# Sensing.net
KiCad netlist of a schematic drawn in Altium Designer
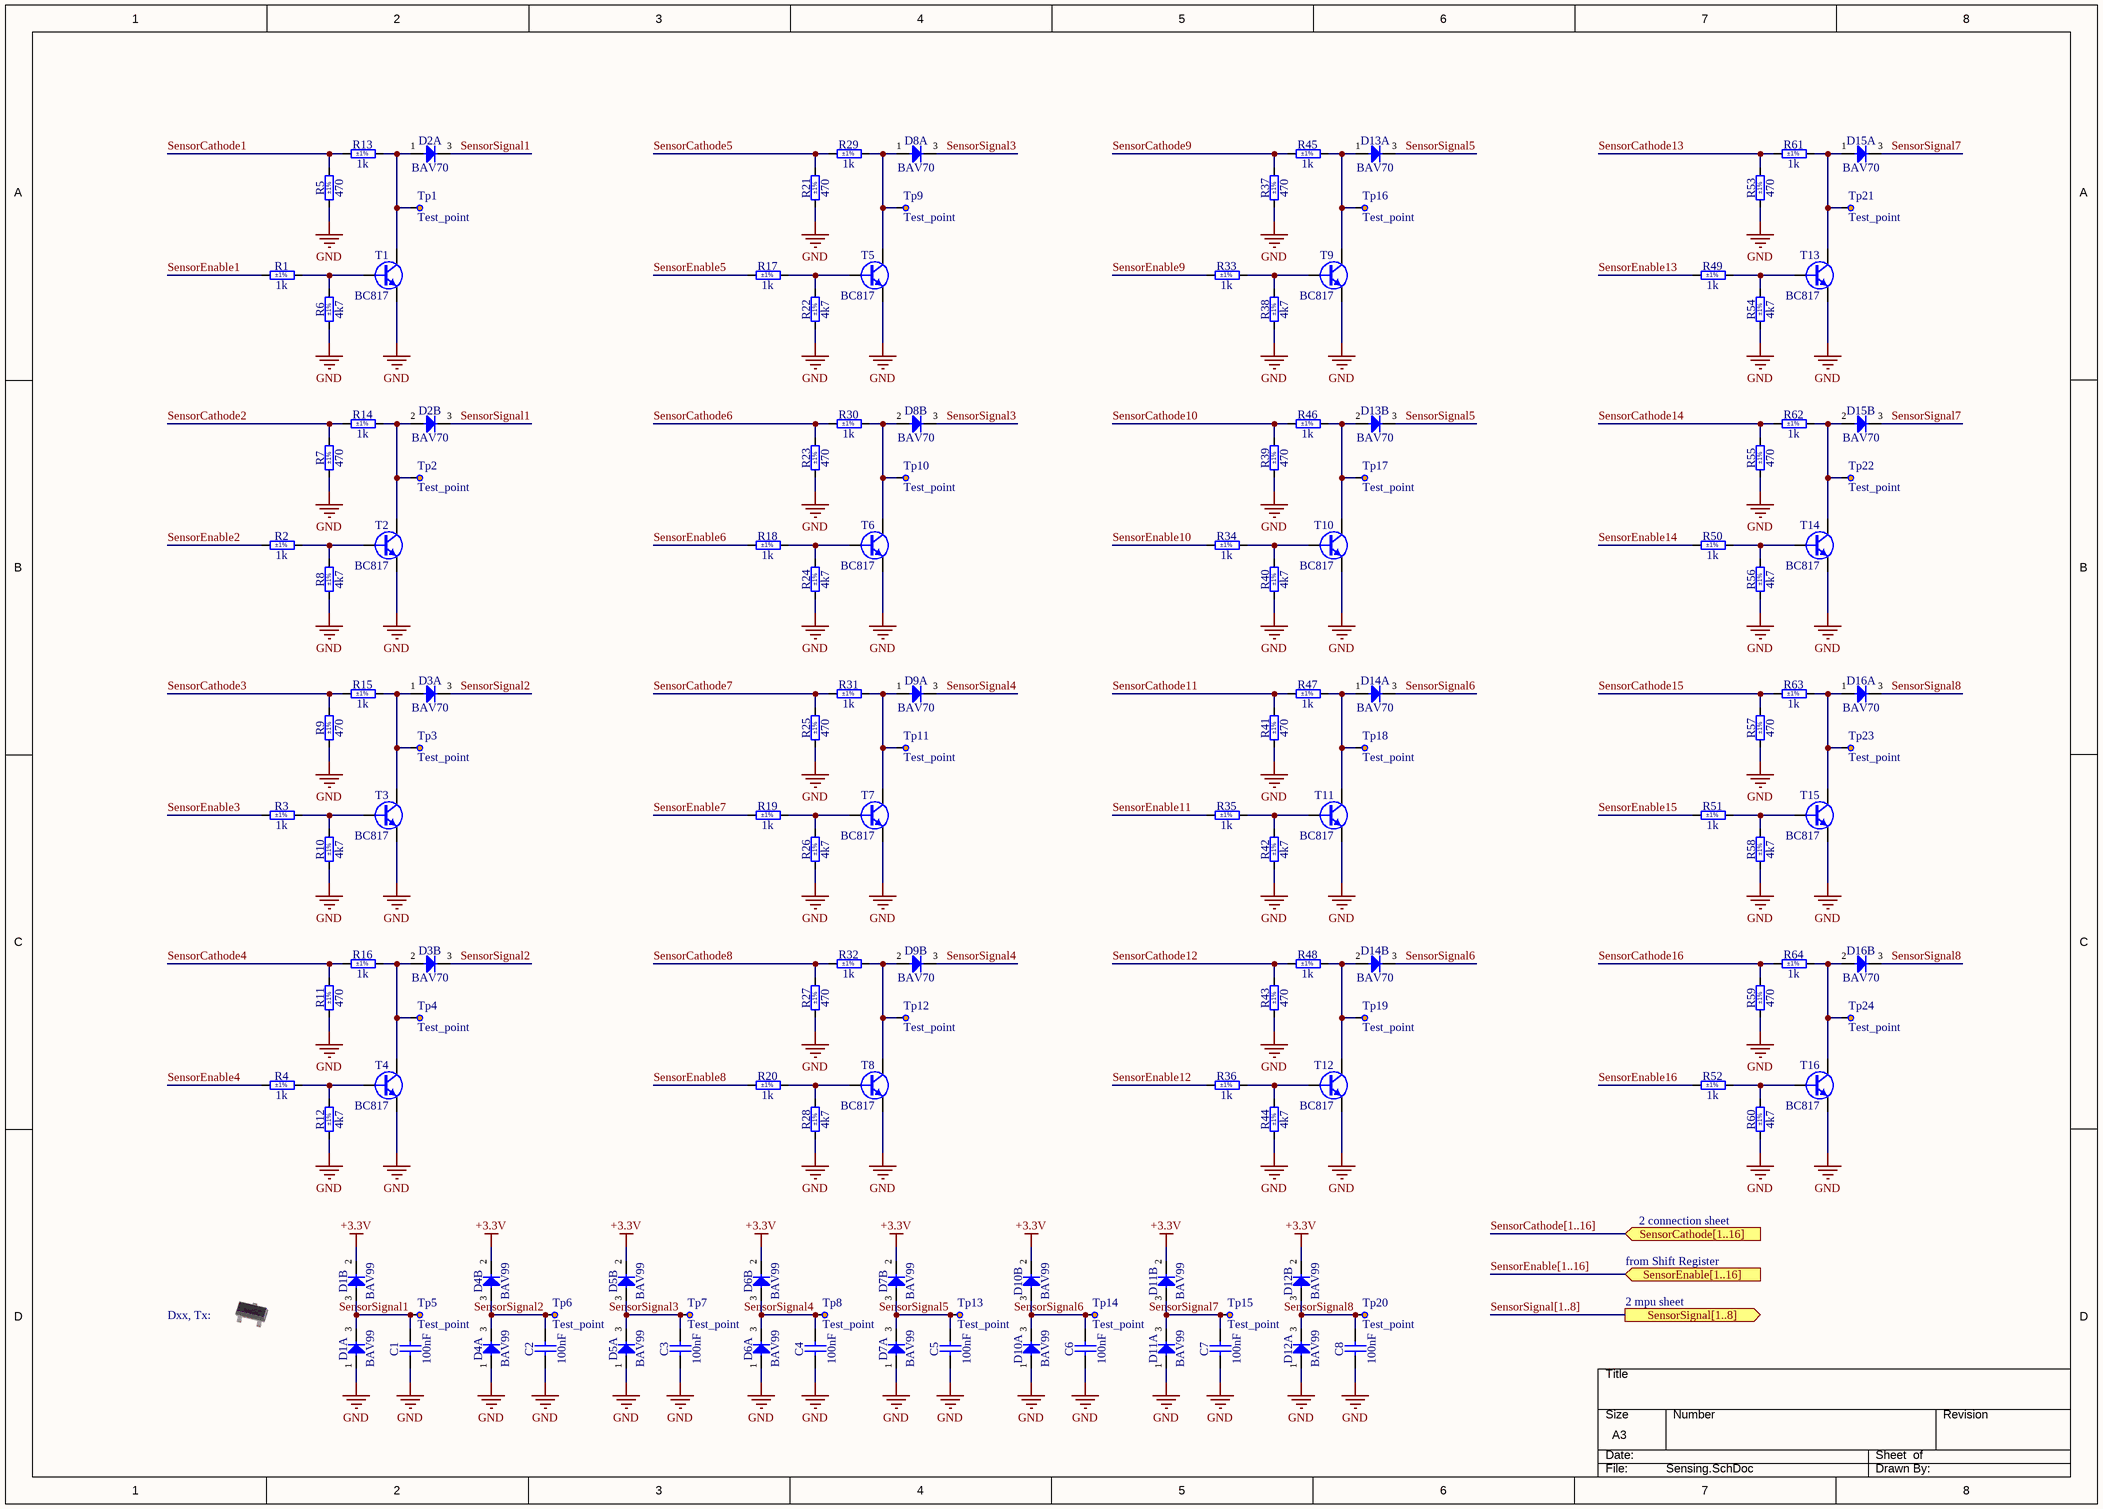
[diagram p0: Sensing.SchDoc]

(export (version "E")
  (design (tool "Eeschema 10.0.6"))
  (components
    (comp (ref "C1")
      (value "100nF")
      (footprint "CAPC1608X87N")
      (description "Non-polarised capacitor")
      (fields
        (field (name "PART NUMBER") "CC0603_100NF_50V_10%_X7R")
        (field (name "VOLTAGE") "50V")
        (field (name "AUTHOR") "CERN DEM JLC")
      )
      (libsource (lib "Capacitors") (part "Capacitor - non polarized"))
    )
    (comp (ref "C2")
      (value "100nF")
      (footprint "CAPC1608X87N")
      (description "Non-polarised capacitor")
      (fields
        (field (name "PART NUMBER") "CC0603_100NF_50V_10%_X7R")
        (field (name "VOLTAGE") "50V")
        (field (name "AUTHOR") "CERN DEM JLC")
      )
      (libsource (lib "Capacitors") (part "Capacitor - non polarized"))
    )
    (comp (ref "C3")
      (value "100nF")
      (footprint "CAPC1608X87N")
      (description "Non-polarised capacitor")
      (fields
        (field (name "PART NUMBER") "CC0603_100NF_50V_10%_X7R")
        (field (name "VOLTAGE") "50V")
        (field (name "AUTHOR") "CERN DEM JLC")
      )
      (libsource (lib "Capacitors") (part "Capacitor - non polarized"))
    )
    (comp (ref "C4")
      (value "100nF")
      (footprint "CAPC1608X87N")
      (description "Non-polarised capacitor")
      (fields
        (field (name "PART NUMBER") "CC0603_100NF_50V_10%_X7R")
        (field (name "VOLTAGE") "50V")
        (field (name "AUTHOR") "CERN DEM JLC")
      )
      (libsource (lib "Capacitors") (part "Capacitor - non polarized"))
    )
    (comp (ref "C5")
      (value "100nF")
      (footprint "CAPC1608X87N")
      (description "Non-polarised capacitor")
      (fields
        (field (name "PART NUMBER") "CC0603_100NF_50V_10%_X7R")
        (field (name "VOLTAGE") "50V")
        (field (name "AUTHOR") "CERN DEM JLC")
      )
      (libsource (lib "Capacitors") (part "Capacitor - non polarized"))
    )
    (comp (ref "C6")
      (value "100nF")
      (footprint "CAPC1608X87N")
      (description "Non-polarised capacitor")
      (fields
        (field (name "PART NUMBER") "CC0603_100NF_50V_10%_X7R")
        (field (name "VOLTAGE") "50V")
        (field (name "AUTHOR") "CERN DEM JLC")
      )
      (libsource (lib "Capacitors") (part "Capacitor - non polarized"))
    )
    (comp (ref "C7")
      (value "100nF")
      (footprint "CAPC1608X87N")
      (description "Non-polarised capacitor")
      (fields
        (field (name "PART NUMBER") "CC0603_100NF_50V_10%_X7R")
        (field (name "VOLTAGE") "50V")
        (field (name "AUTHOR") "CERN DEM JLC")
      )
      (libsource (lib "Capacitors") (part "Capacitor - non polarized"))
    )
    (comp (ref "C8")
      (value "100nF")
      (footprint "CAPC1608X87N")
      (description "Non-polarised capacitor")
      (fields
        (field (name "PART NUMBER") "CC0603_100NF_50V_10%_X7R")
        (field (name "VOLTAGE") "50V")
        (field (name "AUTHOR") "CERN DEM JLC")
      )
      (libsource (lib "Capacitors") (part "Capacitor - non polarized"))
    )
    (comp (ref "D1")
      (value "BAV99")
      (footprint "SOT95P240X110-3N")
      (description "Serial Diode")
      (fields
        (field (name "VOLTAGE") "70V")
        (field (name "POWER") "350mW")
        (field (name "AUTHOR") "CERN DEM JLC")
      )
      (libsource (lib "ICs And Semiconductors") (part "Diode x2 A1C3_A3C2"))
    )
    (comp (ref "D2")
      (value "BAV70")
      (footprint "SOT95P240X110-3N")
      (description "Dual Common Cathode Diodes")
      (fields
        (field (name "VOLTAGE") "100V")
        (field (name "MANUFACTURER") "NXP SEMICONDUCTORS")
        (field (name "AUTHOR") "CERN DEM JLC")
      )
      (libsource (lib "ICs And Semiconductors") (part "Diode x2 A1C3_A2C3"))
    )
    (comp (ref "D3")
      (value "BAV70")
      (footprint "SOT95P240X110-3N")
      (description "Dual Common Cathode Diodes")
      (fields
        (field (name "VOLTAGE") "100V")
        (field (name "MANUFACTURER") "NXP SEMICONDUCTORS")
        (field (name "AUTHOR") "CERN DEM JLC")
      )
      (libsource (lib "ICs And Semiconductors") (part "Diode x2 A1C3_A2C3"))
    )
    (comp (ref "D4")
      (value "BAV99")
      (footprint "SOT95P240X110-3N")
      (description "Serial Diode")
      (fields
        (field (name "VOLTAGE") "70V")
        (field (name "POWER") "350mW")
        (field (name "AUTHOR") "CERN DEM JLC")
      )
      (libsource (lib "ICs And Semiconductors") (part "Diode x2 A1C3_A3C2"))
    )
    (comp (ref "D5")
      (value "BAV99")
      (footprint "SOT95P240X110-3N")
      (description "Serial Diode")
      (fields
        (field (name "VOLTAGE") "70V")
        (field (name "POWER") "350mW")
        (field (name "AUTHOR") "CERN DEM JLC")
      )
      (libsource (lib "ICs And Semiconductors") (part "Diode x2 A1C3_A3C2"))
    )
    (comp (ref "D6")
      (value "BAV99")
      (footprint "SOT95P240X110-3N")
      (description "Serial Diode")
      (fields
        (field (name "VOLTAGE") "70V")
        (field (name "POWER") "350mW")
        (field (name "AUTHOR") "CERN DEM JLC")
      )
      (libsource (lib "ICs And Semiconductors") (part "Diode x2 A1C3_A3C2"))
    )
    (comp (ref "D7")
      (value "BAV99")
      (footprint "SOT95P240X110-3N")
      (description "Serial Diode")
      (fields
        (field (name "VOLTAGE") "70V")
        (field (name "POWER") "350mW")
        (field (name "AUTHOR") "CERN DEM JLC")
      )
      (libsource (lib "ICs And Semiconductors") (part "Diode x2 A1C3_A3C2"))
    )
    (comp (ref "D8")
      (value "BAV70")
      (footprint "SOT95P240X110-3N")
      (description "Dual Common Cathode Diodes")
      (fields
        (field (name "VOLTAGE") "100V")
        (field (name "MANUFACTURER") "NXP SEMICONDUCTORS")
        (field (name "AUTHOR") "CERN DEM JLC")
      )
      (libsource (lib "ICs And Semiconductors") (part "Diode x2 A1C3_A2C3"))
    )
    (comp (ref "D9")
      (value "BAV70")
      (footprint "SOT95P240X110-3N")
      (description "Dual Common Cathode Diodes")
      (fields
        (field (name "VOLTAGE") "100V")
        (field (name "MANUFACTURER") "NXP SEMICONDUCTORS")
        (field (name "AUTHOR") "CERN DEM JLC")
      )
      (libsource (lib "ICs And Semiconductors") (part "Diode x2 A1C3_A2C3"))
    )
    (comp (ref "D10")
      (value "BAV99")
      (footprint "SOT95P240X110-3N")
      (description "Serial Diode")
      (fields
        (field (name "VOLTAGE") "70V")
        (field (name "POWER") "350mW")
        (field (name "AUTHOR") "CERN DEM JLC")
      )
      (libsource (lib "ICs And Semiconductors") (part "Diode x2 A1C3_A3C2"))
    )
    (comp (ref "D11")
      (value "BAV99")
      (footprint "SOT95P240X110-3N")
      (description "Serial Diode")
      (fields
        (field (name "VOLTAGE") "70V")
        (field (name "POWER") "350mW")
        (field (name "AUTHOR") "CERN DEM JLC")
      )
      (libsource (lib "ICs And Semiconductors") (part "Diode x2 A1C3_A3C2"))
    )
    (comp (ref "D12")
      (value "BAV99")
      (footprint "SOT95P240X110-3N")
      (description "Serial Diode")
      (fields
        (field (name "VOLTAGE") "70V")
        (field (name "POWER") "350mW")
        (field (name "AUTHOR") "CERN DEM JLC")
      )
      (libsource (lib "ICs And Semiconductors") (part "Diode x2 A1C3_A3C2"))
    )
    (comp (ref "D13")
      (value "BAV70")
      (footprint "SOT95P240X110-3N")
      (description "Dual Common Cathode Diodes")
      (fields
        (field (name "VOLTAGE") "100V")
        (field (name "MANUFACTURER") "NXP SEMICONDUCTORS")
        (field (name "AUTHOR") "CERN DEM JLC")
      )
      (libsource (lib "ICs And Semiconductors") (part "Diode x2 A1C3_A2C3"))
    )
    (comp (ref "D14")
      (value "BAV70")
      (footprint "SOT95P240X110-3N")
      (description "Dual Common Cathode Diodes")
      (fields
        (field (name "VOLTAGE") "100V")
        (field (name "MANUFACTURER") "NXP SEMICONDUCTORS")
        (field (name "AUTHOR") "CERN DEM JLC")
      )
      (libsource (lib "ICs And Semiconductors") (part "Diode x2 A1C3_A2C3"))
    )
    (comp (ref "D15")
      (value "BAV70")
      (footprint "SOT95P240X110-3N")
      (description "Dual Common Cathode Diodes")
      (fields
        (field (name "VOLTAGE") "100V")
        (field (name "MANUFACTURER") "NXP SEMICONDUCTORS")
        (field (name "AUTHOR") "CERN DEM JLC")
      )
      (libsource (lib "ICs And Semiconductors") (part "Diode x2 A1C3_A2C3"))
    )
    (comp (ref "D16")
      (value "BAV70")
      (footprint "SOT95P240X110-3N")
      (description "Dual Common Cathode Diodes")
      (fields
        (field (name "VOLTAGE") "100V")
        (field (name "MANUFACTURER") "NXP SEMICONDUCTORS")
        (field (name "AUTHOR") "CERN DEM JLC")
      )
      (libsource (lib "ICs And Semiconductors") (part "Diode x2 A1C3_A2C3"))
    )
    (comp (ref "R1")
      (value "1k")
      (footprint "RESC1608X55N")
      (description "Resistor - 1%")
      (fields
        (field (name "TOLERANCE") "±1%")
        (field (name "PART NUMBER") "R0603_1K_1%_0.1W_100PPM")
        (field (name "POWER") "0.1W")
        (field (name "AUTHOR") "CERN DEM JLC")
      )
      (libsource (lib "Resistors") (part "Resistor - 1%"))
    )
    (comp (ref "R2")
      (value "1k")
      (footprint "RESC1608X55N")
      (description "Resistor - 1%")
      (fields
        (field (name "TOLERANCE") "±1%")
        (field (name "PART NUMBER") "R0603_1K_1%_0.1W_100PPM")
        (field (name "POWER") "0.1W")
        (field (name "AUTHOR") "CERN DEM JLC")
      )
      (libsource (lib "Resistors") (part "Resistor - 1%"))
    )
    (comp (ref "R3")
      (value "1k")
      (footprint "RESC1608X55N")
      (description "Resistor - 1%")
      (fields
        (field (name "TOLERANCE") "±1%")
        (field (name "PART NUMBER") "R0603_1K_1%_0.1W_100PPM")
        (field (name "POWER") "0.1W")
        (field (name "AUTHOR") "CERN DEM JLC")
      )
      (libsource (lib "Resistors") (part "Resistor - 1%"))
    )
    (comp (ref "R4")
      (value "1k")
      (footprint "RESC1608X55N")
      (description "Resistor - 1%")
      (fields
        (field (name "TOLERANCE") "±1%")
        (field (name "PART NUMBER") "R0603_1K_1%_0.1W_100PPM")
        (field (name "POWER") "0.1W")
        (field (name "AUTHOR") "CERN DEM JLC")
      )
      (libsource (lib "Resistors") (part "Resistor - 1%"))
    )
    (comp (ref "R5")
      (value "470")
      (footprint "RESC6331X70N")
      (description "Resistor - 1%")
      (fields
        (field (name "TOLERANCE") "±1%")
        (field (name "PART NUMBER") "R2512_470R_1%_1W_100PPM")
        (field (name "POWER") "1W")
        (field (name "AUTHOR") "CERN DEM BC")
      )
      (libsource (lib "Resistors") (part "Resistor - 1%"))
    )
    (comp (ref "R6")
      (value "4k7")
      (footprint "RESC1608X55N")
      (description "Resistor - 1%")
      (fields
        (field (name "TOLERANCE") "±1%")
        (field (name "PART NUMBER") "R0603_4K7_1%_0.1W_100PPM")
        (field (name "POWER") "0.1W")
        (field (name "AUTHOR") "CERN DEM JLC")
      )
      (libsource (lib "Resistors") (part "Resistor - 1%"))
    )
    (comp (ref "R7")
      (value "470")
      (footprint "RESC6331X70N")
      (description "Resistor - 1%")
      (fields
        (field (name "TOLERANCE") "±1%")
        (field (name "PART NUMBER") "R2512_470R_1%_1W_100PPM")
        (field (name "POWER") "1W")
        (field (name "AUTHOR") "CERN DEM BC")
      )
      (libsource (lib "Resistors") (part "Resistor - 1%"))
    )
    (comp (ref "R8")
      (value "4k7")
      (footprint "RESC1608X55N")
      (description "Resistor - 1%")
      (fields
        (field (name "TOLERANCE") "±1%")
        (field (name "PART NUMBER") "R0603_4K7_1%_0.1W_100PPM")
        (field (name "POWER") "0.1W")
        (field (name "AUTHOR") "CERN DEM JLC")
      )
      (libsource (lib "Resistors") (part "Resistor - 1%"))
    )
    (comp (ref "R9")
      (value "470")
      (footprint "RESC6331X70N")
      (description "Resistor - 1%")
      (fields
        (field (name "TOLERANCE") "±1%")
        (field (name "PART NUMBER") "R2512_470R_1%_1W_100PPM")
        (field (name "POWER") "1W")
        (field (name "AUTHOR") "CERN DEM BC")
      )
      (libsource (lib "Resistors") (part "Resistor - 1%"))
    )
    (comp (ref "R10")
      (value "4k7")
      (footprint "RESC1608X55N")
      (description "Resistor - 1%")
      (fields
        (field (name "TOLERANCE") "±1%")
        (field (name "PART NUMBER") "R0603_4K7_1%_0.1W_100PPM")
        (field (name "POWER") "0.1W")
        (field (name "AUTHOR") "CERN DEM JLC")
      )
      (libsource (lib "Resistors") (part "Resistor - 1%"))
    )
    (comp (ref "R11")
      (value "470")
      (footprint "RESC6331X70N")
      (description "Resistor - 1%")
      (fields
        (field (name "TOLERANCE") "±1%")
        (field (name "PART NUMBER") "R2512_470R_1%_1W_100PPM")
        (field (name "POWER") "1W")
        (field (name "AUTHOR") "CERN DEM BC")
      )
      (libsource (lib "Resistors") (part "Resistor - 1%"))
    )
    (comp (ref "R12")
      (value "4k7")
      (footprint "RESC1608X55N")
      (description "Resistor - 1%")
      (fields
        (field (name "TOLERANCE") "±1%")
        (field (name "PART NUMBER") "R0603_4K7_1%_0.1W_100PPM")
        (field (name "POWER") "0.1W")
        (field (name "AUTHOR") "CERN DEM JLC")
      )
      (libsource (lib "Resistors") (part "Resistor - 1%"))
    )
    (comp (ref "R13")
      (value "1k")
      (footprint "RESC1608X55N")
      (description "Resistor - 1%")
      (fields
        (field (name "TOLERANCE") "±1%")
        (field (name "PART NUMBER") "R0603_1K_1%_0.1W_100PPM")
        (field (name "POWER") "0.1W")
        (field (name "AUTHOR") "CERN DEM JLC")
      )
      (libsource (lib "Resistors") (part "Resistor - 1%"))
    )
    (comp (ref "R14")
      (value "1k")
      (footprint "RESC1608X55N")
      (description "Resistor - 1%")
      (fields
        (field (name "TOLERANCE") "±1%")
        (field (name "PART NUMBER") "R0603_1K_1%_0.1W_100PPM")
        (field (name "POWER") "0.1W")
        (field (name "AUTHOR") "CERN DEM JLC")
      )
      (libsource (lib "Resistors") (part "Resistor - 1%"))
    )
    (comp (ref "R15")
      (value "1k")
      (footprint "RESC1608X55N")
      (description "Resistor - 1%")
      (fields
        (field (name "TOLERANCE") "±1%")
        (field (name "PART NUMBER") "R0603_1K_1%_0.1W_100PPM")
        (field (name "POWER") "0.1W")
        (field (name "AUTHOR") "CERN DEM JLC")
      )
      (libsource (lib "Resistors") (part "Resistor - 1%"))
    )
    (comp (ref "R16")
      (value "1k")
      (footprint "RESC1608X55N")
      (description "Resistor - 1%")
      (fields
        (field (name "TOLERANCE") "±1%")
        (field (name "PART NUMBER") "R0603_1K_1%_0.1W_100PPM")
        (field (name "POWER") "0.1W")
        (field (name "AUTHOR") "CERN DEM JLC")
      )
      (libsource (lib "Resistors") (part "Resistor - 1%"))
    )
    (comp (ref "R17")
      (value "1k")
      (footprint "RESC1608X55N")
      (description "Resistor - 1%")
      (fields
        (field (name "TOLERANCE") "±1%")
        (field (name "PART NUMBER") "R0603_1K_1%_0.1W_100PPM")
        (field (name "POWER") "0.1W")
        (field (name "AUTHOR") "CERN DEM JLC")
      )
      (libsource (lib "Resistors") (part "Resistor - 1%"))
    )
    (comp (ref "R18")
      (value "1k")
      (footprint "RESC1608X55N")
      (description "Resistor - 1%")
      (fields
        (field (name "TOLERANCE") "±1%")
        (field (name "PART NUMBER") "R0603_1K_1%_0.1W_100PPM")
        (field (name "POWER") "0.1W")
        (field (name "AUTHOR") "CERN DEM JLC")
      )
      (libsource (lib "Resistors") (part "Resistor - 1%"))
    )
    (comp (ref "R19")
      (value "1k")
      (footprint "RESC1608X55N")
      (description "Resistor - 1%")
      (fields
        (field (name "TOLERANCE") "±1%")
        (field (name "PART NUMBER") "R0603_1K_1%_0.1W_100PPM")
        (field (name "POWER") "0.1W")
        (field (name "AUTHOR") "CERN DEM JLC")
      )
      (libsource (lib "Resistors") (part "Resistor - 1%"))
    )
    (comp (ref "R20")
      (value "1k")
      (footprint "RESC1608X55N")
      (description "Resistor - 1%")
      (fields
        (field (name "TOLERANCE") "±1%")
        (field (name "PART NUMBER") "R0603_1K_1%_0.1W_100PPM")
        (field (name "POWER") "0.1W")
        (field (name "AUTHOR") "CERN DEM JLC")
      )
      (libsource (lib "Resistors") (part "Resistor - 1%"))
    )
    (comp (ref "R21")
      (value "470")
      (footprint "RESC6331X70N")
      (description "Resistor - 1%")
      (fields
        (field (name "TOLERANCE") "±1%")
        (field (name "PART NUMBER") "R2512_470R_1%_1W_100PPM")
        (field (name "POWER") "1W")
        (field (name "AUTHOR") "CERN DEM BC")
      )
      (libsource (lib "Resistors") (part "Resistor - 1%"))
    )
    (comp (ref "R22")
      (value "4k7")
      (footprint "RESC1608X55N")
      (description "Resistor - 1%")
      (fields
        (field (name "TOLERANCE") "±1%")
        (field (name "PART NUMBER") "R0603_4K7_1%_0.1W_100PPM")
        (field (name "POWER") "0.1W")
        (field (name "AUTHOR") "CERN DEM JLC")
      )
      (libsource (lib "Resistors") (part "Resistor - 1%"))
    )
    (comp (ref "R23")
      (value "470")
      (footprint "RESC6331X70N")
      (description "Resistor - 1%")
      (fields
        (field (name "TOLERANCE") "±1%")
        (field (name "PART NUMBER") "R2512_470R_1%_1W_100PPM")
        (field (name "POWER") "1W")
        (field (name "AUTHOR") "CERN DEM BC")
      )
      (libsource (lib "Resistors") (part "Resistor - 1%"))
    )
    (comp (ref "R24")
      (value "4k7")
      (footprint "RESC1608X55N")
      (description "Resistor - 1%")
      (fields
        (field (name "TOLERANCE") "±1%")
        (field (name "PART NUMBER") "R0603_4K7_1%_0.1W_100PPM")
        (field (name "POWER") "0.1W")
        (field (name "AUTHOR") "CERN DEM JLC")
      )
      (libsource (lib "Resistors") (part "Resistor - 1%"))
    )
    (comp (ref "R25")
      (value "470")
      (footprint "RESC6331X70N")
      (description "Resistor - 1%")
      (fields
        (field (name "TOLERANCE") "±1%")
        (field (name "PART NUMBER") "R2512_470R_1%_1W_100PPM")
        (field (name "POWER") "1W")
        (field (name "AUTHOR") "CERN DEM BC")
      )
      (libsource (lib "Resistors") (part "Resistor - 1%"))
    )
    (comp (ref "R26")
      (value "4k7")
      (footprint "RESC1608X55N")
      (description "Resistor - 1%")
      (fields
        (field (name "TOLERANCE") "±1%")
        (field (name "PART NUMBER") "R0603_4K7_1%_0.1W_100PPM")
        (field (name "POWER") "0.1W")
        (field (name "AUTHOR") "CERN DEM JLC")
      )
      (libsource (lib "Resistors") (part "Resistor - 1%"))
    )
    (comp (ref "R27")
      (value "470")
      (footprint "RESC6331X70N")
      (description "Resistor - 1%")
      (fields
        (field (name "TOLERANCE") "±1%")
        (field (name "PART NUMBER") "R2512_470R_1%_1W_100PPM")
        (field (name "POWER") "1W")
        (field (name "AUTHOR") "CERN DEM BC")
      )
      (libsource (lib "Resistors") (part "Resistor - 1%"))
    )
    (comp (ref "R28")
      (value "4k7")
      (footprint "RESC1608X55N")
      (description "Resistor - 1%")
      (fields
        (field (name "TOLERANCE") "±1%")
        (field (name "PART NUMBER") "R0603_4K7_1%_0.1W_100PPM")
        (field (name "POWER") "0.1W")
        (field (name "AUTHOR") "CERN DEM JLC")
      )
      (libsource (lib "Resistors") (part "Resistor - 1%"))
    )
    (comp (ref "R29")
      (value "1k")
      (footprint "RESC1608X55N")
      (description "Resistor - 1%")
      (fields
        (field (name "TOLERANCE") "±1%")
        (field (name "PART NUMBER") "R0603_1K_1%_0.1W_100PPM")
        (field (name "POWER") "0.1W")
        (field (name "AUTHOR") "CERN DEM JLC")
      )
      (libsource (lib "Resistors") (part "Resistor - 1%"))
    )
    (comp (ref "R30")
      (value "1k")
      (footprint "RESC1608X55N")
      (description "Resistor - 1%")
      (fields
        (field (name "TOLERANCE") "±1%")
        (field (name "PART NUMBER") "R0603_1K_1%_0.1W_100PPM")
        (field (name "POWER") "0.1W")
        (field (name "AUTHOR") "CERN DEM JLC")
      )
      (libsource (lib "Resistors") (part "Resistor - 1%"))
    )
    (comp (ref "R31")
      (value "1k")
      (footprint "RESC1608X55N")
      (description "Resistor - 1%")
      (fields
        (field (name "TOLERANCE") "±1%")
        (field (name "PART NUMBER") "R0603_1K_1%_0.1W_100PPM")
        (field (name "POWER") "0.1W")
        (field (name "AUTHOR") "CERN DEM JLC")
      )
      (libsource (lib "Resistors") (part "Resistor - 1%"))
    )
    (comp (ref "R32")
      (value "1k")
      (footprint "RESC1608X55N")
      (description "Resistor - 1%")
      (fields
        (field (name "TOLERANCE") "±1%")
        (field (name "PART NUMBER") "R0603_1K_1%_0.1W_100PPM")
        (field (name "POWER") "0.1W")
        (field (name "AUTHOR") "CERN DEM JLC")
      )
      (libsource (lib "Resistors") (part "Resistor - 1%"))
    )
    (comp (ref "R33")
      (value "1k")
      (footprint "RESC1608X55N")
      (description "Resistor - 1%")
      (fields
        (field (name "TOLERANCE") "±1%")
        (field (name "PART NUMBER") "R0603_1K_1%_0.1W_100PPM")
        (field (name "POWER") "0.1W")
        (field (name "AUTHOR") "CERN DEM JLC")
      )
      (libsource (lib "Resistors") (part "Resistor - 1%"))
    )
    (comp (ref "R34")
      (value "1k")
      (footprint "RESC1608X55N")
      (description "Resistor - 1%")
      (fields
        (field (name "TOLERANCE") "±1%")
        (field (name "PART NUMBER") "R0603_1K_1%_0.1W_100PPM")
        (field (name "POWER") "0.1W")
        (field (name "AUTHOR") "CERN DEM JLC")
      )
      (libsource (lib "Resistors") (part "Resistor - 1%"))
    )
    (comp (ref "R35")
      (value "1k")
      (footprint "RESC1608X55N")
      (description "Resistor - 1%")
      (fields
        (field (name "TOLERANCE") "±1%")
        (field (name "PART NUMBER") "R0603_1K_1%_0.1W_100PPM")
        (field (name "POWER") "0.1W")
        (field (name "AUTHOR") "CERN DEM JLC")
      )
      (libsource (lib "Resistors") (part "Resistor - 1%"))
    )
    (comp (ref "R36")
      (value "1k")
      (footprint "RESC1608X55N")
      (description "Resistor - 1%")
      (fields
        (field (name "TOLERANCE") "±1%")
        (field (name "PART NUMBER") "R0603_1K_1%_0.1W_100PPM")
        (field (name "POWER") "0.1W")
        (field (name "AUTHOR") "CERN DEM JLC")
      )
      (libsource (lib "Resistors") (part "Resistor - 1%"))
    )
    (comp (ref "R37")
      (value "470")
      (footprint "RESC6331X70N")
      (description "Resistor - 1%")
      (fields
        (field (name "TOLERANCE") "±1%")
        (field (name "PART NUMBER") "R2512_470R_1%_1W_100PPM")
        (field (name "POWER") "1W")
        (field (name "AUTHOR") "CERN DEM BC")
      )
      (libsource (lib "Resistors") (part "Resistor - 1%"))
    )
    (comp (ref "R38")
      (value "4k7")
      (footprint "RESC1608X55N")
      (description "Resistor - 1%")
      (fields
        (field (name "TOLERANCE") "±1%")
        (field (name "PART NUMBER") "R0603_4K7_1%_0.1W_100PPM")
        (field (name "POWER") "0.1W")
        (field (name "AUTHOR") "CERN DEM JLC")
      )
      (libsource (lib "Resistors") (part "Resistor - 1%"))
    )
    (comp (ref "R39")
      (value "470")
      (footprint "RESC6331X70N")
      (description "Resistor - 1%")
      (fields
        (field (name "TOLERANCE") "±1%")
        (field (name "PART NUMBER") "R2512_470R_1%_1W_100PPM")
        (field (name "POWER") "1W")
        (field (name "AUTHOR") "CERN DEM BC")
      )
      (libsource (lib "Resistors") (part "Resistor - 1%"))
    )
    (comp (ref "R40")
      (value "4k7")
      (footprint "RESC1608X55N")
      (description "Resistor - 1%")
      (fields
        (field (name "TOLERANCE") "±1%")
        (field (name "PART NUMBER") "R0603_4K7_1%_0.1W_100PPM")
        (field (name "POWER") "0.1W")
        (field (name "AUTHOR") "CERN DEM JLC")
      )
      (libsource (lib "Resistors") (part "Resistor - 1%"))
    )
    (comp (ref "R41")
      (value "470")
      (footprint "RESC6331X70N")
      (description "Resistor - 1%")
      (fields
        (field (name "TOLERANCE") "±1%")
        (field (name "PART NUMBER") "R2512_470R_1%_1W_100PPM")
        (field (name "POWER") "1W")
        (field (name "AUTHOR") "CERN DEM BC")
      )
      (libsource (lib "Resistors") (part "Resistor - 1%"))
    )
    (comp (ref "R42")
      (value "4k7")
      (footprint "RESC1608X55N")
      (description "Resistor - 1%")
      (fields
        (field (name "TOLERANCE") "±1%")
        (field (name "PART NUMBER") "R0603_4K7_1%_0.1W_100PPM")
        (field (name "POWER") "0.1W")
        (field (name "AUTHOR") "CERN DEM JLC")
      )
      (libsource (lib "Resistors") (part "Resistor - 1%"))
    )
    (comp (ref "R43")
      (value "470")
      (footprint "RESC6331X70N")
      (description "Resistor - 1%")
      (fields
        (field (name "TOLERANCE") "±1%")
        (field (name "PART NUMBER") "R2512_470R_1%_1W_100PPM")
        (field (name "POWER") "1W")
        (field (name "AUTHOR") "CERN DEM BC")
      )
      (libsource (lib "Resistors") (part "Resistor - 1%"))
    )
    (comp (ref "R44")
      (value "4k7")
      (footprint "RESC1608X55N")
      (description "Resistor - 1%")
      (fields
        (field (name "TOLERANCE") "±1%")
        (field (name "PART NUMBER") "R0603_4K7_1%_0.1W_100PPM")
        (field (name "POWER") "0.1W")
        (field (name "AUTHOR") "CERN DEM JLC")
      )
      (libsource (lib "Resistors") (part "Resistor - 1%"))
    )
    (comp (ref "R45")
      (value "1k")
      (footprint "RESC1608X55N")
      (description "Resistor - 1%")
      (fields
        (field (name "TOLERANCE") "±1%")
        (field (name "PART NUMBER") "R0603_1K_1%_0.1W_100PPM")
        (field (name "POWER") "0.1W")
        (field (name "AUTHOR") "CERN DEM JLC")
      )
      (libsource (lib "Resistors") (part "Resistor - 1%"))
    )
    (comp (ref "R46")
      (value "1k")
      (footprint "RESC1608X55N")
      (description "Resistor - 1%")
      (fields
        (field (name "TOLERANCE") "±1%")
        (field (name "PART NUMBER") "R0603_1K_1%_0.1W_100PPM")
        (field (name "POWER") "0.1W")
        (field (name "AUTHOR") "CERN DEM JLC")
      )
      (libsource (lib "Resistors") (part "Resistor - 1%"))
    )
    (comp (ref "R47")
      (value "1k")
      (footprint "RESC1608X55N")
      (description "Resistor - 1%")
      (fields
        (field (name "TOLERANCE") "±1%")
        (field (name "PART NUMBER") "R0603_1K_1%_0.1W_100PPM")
        (field (name "POWER") "0.1W")
        (field (name "AUTHOR") "CERN DEM JLC")
      )
      (libsource (lib "Resistors") (part "Resistor - 1%"))
    )
    (comp (ref "R48")
      (value "1k")
      (footprint "RESC1608X55N")
      (description "Resistor - 1%")
      (fields
        (field (name "TOLERANCE") "±1%")
        (field (name "PART NUMBER") "R0603_1K_1%_0.1W_100PPM")
        (field (name "POWER") "0.1W")
        (field (name "AUTHOR") "CERN DEM JLC")
      )
      (libsource (lib "Resistors") (part "Resistor - 1%"))
    )
    (comp (ref "R49")
      (value "1k")
      (footprint "RESC1608X55N")
      (description "Resistor - 1%")
      (fields
        (field (name "TOLERANCE") "±1%")
        (field (name "PART NUMBER") "R0603_1K_1%_0.1W_100PPM")
        (field (name "POWER") "0.1W")
        (field (name "AUTHOR") "CERN DEM JLC")
      )
      (libsource (lib "Resistors") (part "Resistor - 1%"))
    )
    (comp (ref "R50")
      (value "1k")
      (footprint "RESC1608X55N")
      (description "Resistor - 1%")
      (fields
        (field (name "TOLERANCE") "±1%")
        (field (name "PART NUMBER") "R0603_1K_1%_0.1W_100PPM")
        (field (name "POWER") "0.1W")
        (field (name "AUTHOR") "CERN DEM JLC")
      )
      (libsource (lib "Resistors") (part "Resistor - 1%"))
    )
    (comp (ref "R51")
      (value "1k")
      (footprint "RESC1608X55N")
      (description "Resistor - 1%")
      (fields
        (field (name "TOLERANCE") "±1%")
        (field (name "PART NUMBER") "R0603_1K_1%_0.1W_100PPM")
        (field (name "POWER") "0.1W")
        (field (name "AUTHOR") "CERN DEM JLC")
      )
      (libsource (lib "Resistors") (part "Resistor - 1%"))
    )
    (comp (ref "R52")
      (value "1k")
      (footprint "RESC1608X55N")
      (description "Resistor - 1%")
      (fields
        (field (name "TOLERANCE") "±1%")
        (field (name "PART NUMBER") "R0603_1K_1%_0.1W_100PPM")
        (field (name "POWER") "0.1W")
        (field (name "AUTHOR") "CERN DEM JLC")
      )
      (libsource (lib "Resistors") (part "Resistor - 1%"))
    )
    (comp (ref "R53")
      (value "470")
      (footprint "RESC6331X70N")
      (description "Resistor - 1%")
      (fields
        (field (name "TOLERANCE") "±1%")
        (field (name "PART NUMBER") "R2512_470R_1%_1W_100PPM")
        (field (name "POWER") "1W")
        (field (name "AUTHOR") "CERN DEM BC")
      )
      (libsource (lib "Resistors") (part "Resistor - 1%"))
    )
    (comp (ref "R54")
      (value "4k7")
      (footprint "RESC1608X55N")
      (description "Resistor - 1%")
      (fields
        (field (name "TOLERANCE") "±1%")
        (field (name "PART NUMBER") "R0603_4K7_1%_0.1W_100PPM")
        (field (name "POWER") "0.1W")
        (field (name "AUTHOR") "CERN DEM JLC")
      )
      (libsource (lib "Resistors") (part "Resistor - 1%"))
    )
    (comp (ref "R55")
      (value "470")
      (footprint "RESC6331X70N")
      (description "Resistor - 1%")
      (fields
        (field (name "TOLERANCE") "±1%")
        (field (name "PART NUMBER") "R2512_470R_1%_1W_100PPM")
        (field (name "POWER") "1W")
        (field (name "AUTHOR") "CERN DEM BC")
      )
      (libsource (lib "Resistors") (part "Resistor - 1%"))
    )
    (comp (ref "R56")
      (value "4k7")
      (footprint "RESC1608X55N")
      (description "Resistor - 1%")
      (fields
        (field (name "TOLERANCE") "±1%")
        (field (name "PART NUMBER") "R0603_4K7_1%_0.1W_100PPM")
        (field (name "POWER") "0.1W")
        (field (name "AUTHOR") "CERN DEM JLC")
      )
      (libsource (lib "Resistors") (part "Resistor - 1%"))
    )
    (comp (ref "R57")
      (value "470")
      (footprint "RESC6331X70N")
      (description "Resistor - 1%")
      (fields
        (field (name "TOLERANCE") "±1%")
        (field (name "PART NUMBER") "R2512_470R_1%_1W_100PPM")
        (field (name "POWER") "1W")
        (field (name "AUTHOR") "CERN DEM BC")
      )
      (libsource (lib "Resistors") (part "Resistor - 1%"))
    )
    (comp (ref "R58")
      (value "4k7")
      (footprint "RESC1608X55N")
      (description "Resistor - 1%")
      (fields
        (field (name "TOLERANCE") "±1%")
        (field (name "PART NUMBER") "R0603_4K7_1%_0.1W_100PPM")
        (field (name "POWER") "0.1W")
        (field (name "AUTHOR") "CERN DEM JLC")
      )
      (libsource (lib "Resistors") (part "Resistor - 1%"))
    )
    (comp (ref "R59")
      (value "470")
      (footprint "RESC6331X70N")
      (description "Resistor - 1%")
      (fields
        (field (name "TOLERANCE") "±1%")
        (field (name "PART NUMBER") "R2512_470R_1%_1W_100PPM")
        (field (name "POWER") "1W")
        (field (name "AUTHOR") "CERN DEM BC")
      )
      (libsource (lib "Resistors") (part "Resistor - 1%"))
    )
    (comp (ref "R60")
      (value "4k7")
      (footprint "RESC1608X55N")
      (description "Resistor - 1%")
      (fields
        (field (name "TOLERANCE") "±1%")
        (field (name "PART NUMBER") "R0603_4K7_1%_0.1W_100PPM")
        (field (name "POWER") "0.1W")
        (field (name "AUTHOR") "CERN DEM JLC")
      )
      (libsource (lib "Resistors") (part "Resistor - 1%"))
    )
    (comp (ref "R61")
      (value "1k")
      (footprint "RESC1608X55N")
      (description "Resistor - 1%")
      (fields
        (field (name "TOLERANCE") "±1%")
        (field (name "PART NUMBER") "R0603_1K_1%_0.1W_100PPM")
        (field (name "POWER") "0.1W")
        (field (name "AUTHOR") "CERN DEM JLC")
      )
      (libsource (lib "Resistors") (part "Resistor - 1%"))
    )
    (comp (ref "R62")
      (value "1k")
      (footprint "RESC1608X55N")
      (description "Resistor - 1%")
      (fields
        (field (name "TOLERANCE") "±1%")
        (field (name "PART NUMBER") "R0603_1K_1%_0.1W_100PPM")
        (field (name "POWER") "0.1W")
        (field (name "AUTHOR") "CERN DEM JLC")
      )
      (libsource (lib "Resistors") (part "Resistor - 1%"))
    )
    (comp (ref "R63")
      (value "1k")
      (footprint "RESC1608X55N")
      (description "Resistor - 1%")
      (fields
        (field (name "TOLERANCE") "±1%")
        (field (name "PART NUMBER") "R0603_1K_1%_0.1W_100PPM")
        (field (name "POWER") "0.1W")
        (field (name "AUTHOR") "CERN DEM JLC")
      )
      (libsource (lib "Resistors") (part "Resistor - 1%"))
    )
    (comp (ref "R64")
      (value "1k")
      (footprint "RESC1608X55N")
      (description "Resistor - 1%")
      (fields
        (field (name "TOLERANCE") "±1%")
        (field (name "PART NUMBER") "R0603_1K_1%_0.1W_100PPM")
        (field (name "POWER") "0.1W")
        (field (name "AUTHOR") "CERN DEM JLC")
      )
      (libsource (lib "Resistors") (part "Resistor - 1%"))
    )
    (comp (ref "T1")
      (value "BC817")
      (footprint "SOT95P230X110-3N")
      (description "NPN Transistor")
      (fields (field (name "MANUFACTURER") "NXP SEMICONDUCTORS") (field (name "AUTHOR") "CERN DEM JLC"))
      (libsource (lib "ICs And Semiconductors") (part "NPN B1 E2 C3"))
    )
    (comp (ref "T2")
      (value "BC817")
      (footprint "SOT95P230X110-3N")
      (description "NPN Transistor")
      (fields (field (name "MANUFACTURER") "NXP SEMICONDUCTORS") (field (name "AUTHOR") "CERN DEM JLC"))
      (libsource (lib "ICs And Semiconductors") (part "NPN B1 E2 C3"))
    )
    (comp (ref "T3")
      (value "BC817")
      (footprint "SOT95P230X110-3N")
      (description "NPN Transistor")
      (fields (field (name "MANUFACTURER") "NXP SEMICONDUCTORS") (field (name "AUTHOR") "CERN DEM JLC"))
      (libsource (lib "ICs And Semiconductors") (part "NPN B1 E2 C3"))
    )
    (comp (ref "T4")
      (value "BC817")
      (footprint "SOT95P230X110-3N")
      (description "NPN Transistor")
      (fields (field (name "MANUFACTURER") "NXP SEMICONDUCTORS") (field (name "AUTHOR") "CERN DEM JLC"))
      (libsource (lib "ICs And Semiconductors") (part "NPN B1 E2 C3"))
    )
    (comp (ref "T5")
      (value "BC817")
      (footprint "SOT95P230X110-3N")
      (description "NPN Transistor")
      (fields (field (name "MANUFACTURER") "NXP SEMICONDUCTORS") (field (name "AUTHOR") "CERN DEM JLC"))
      (libsource (lib "ICs And Semiconductors") (part "NPN B1 E2 C3"))
    )
    (comp (ref "T6")
      (value "BC817")
      (footprint "SOT95P230X110-3N")
      (description "NPN Transistor")
      (fields (field (name "MANUFACTURER") "NXP SEMICONDUCTORS") (field (name "AUTHOR") "CERN DEM JLC"))
      (libsource (lib "ICs And Semiconductors") (part "NPN B1 E2 C3"))
    )
    (comp (ref "T7")
      (value "BC817")
      (footprint "SOT95P230X110-3N")
      (description "NPN Transistor")
      (fields (field (name "MANUFACTURER") "NXP SEMICONDUCTORS") (field (name "AUTHOR") "CERN DEM JLC"))
      (libsource (lib "ICs And Semiconductors") (part "NPN B1 E2 C3"))
    )
    (comp (ref "T8")
      (value "BC817")
      (footprint "SOT95P230X110-3N")
      (description "NPN Transistor")
      (fields (field (name "MANUFACTURER") "NXP SEMICONDUCTORS") (field (name "AUTHOR") "CERN DEM JLC"))
      (libsource (lib "ICs And Semiconductors") (part "NPN B1 E2 C3"))
    )
    (comp (ref "T9")
      (value "BC817")
      (footprint "SOT95P230X110-3N")
      (description "NPN Transistor")
      (fields (field (name "MANUFACTURER") "NXP SEMICONDUCTORS") (field (name "AUTHOR") "CERN DEM JLC"))
      (libsource (lib "ICs And Semiconductors") (part "NPN B1 E2 C3"))
    )
    (comp (ref "T10")
      (value "BC817")
      (footprint "SOT95P230X110-3N")
      (description "NPN Transistor")
      (fields (field (name "MANUFACTURER") "NXP SEMICONDUCTORS") (field (name "AUTHOR") "CERN DEM JLC"))
      (libsource (lib "ICs And Semiconductors") (part "NPN B1 E2 C3"))
    )
    (comp (ref "T11")
      (value "BC817")
      (footprint "SOT95P230X110-3N")
      (description "NPN Transistor")
      (fields (field (name "MANUFACTURER") "NXP SEMICONDUCTORS") (field (name "AUTHOR") "CERN DEM JLC"))
      (libsource (lib "ICs And Semiconductors") (part "NPN B1 E2 C3"))
    )
    (comp (ref "T12")
      (value "BC817")
      (footprint "SOT95P230X110-3N")
      (description "NPN Transistor")
      (fields (field (name "MANUFACTURER") "NXP SEMICONDUCTORS") (field (name "AUTHOR") "CERN DEM JLC"))
      (libsource (lib "ICs And Semiconductors") (part "NPN B1 E2 C3"))
    )
    (comp (ref "T13")
      (value "BC817")
      (footprint "SOT95P230X110-3N")
      (description "NPN Transistor")
      (fields (field (name "MANUFACTURER") "NXP SEMICONDUCTORS") (field (name "AUTHOR") "CERN DEM JLC"))
      (libsource (lib "ICs And Semiconductors") (part "NPN B1 E2 C3"))
    )
    (comp (ref "T14")
      (value "BC817")
      (footprint "SOT95P230X110-3N")
      (description "NPN Transistor")
      (fields (field (name "MANUFACTURER") "NXP SEMICONDUCTORS") (field (name "AUTHOR") "CERN DEM JLC"))
      (libsource (lib "ICs And Semiconductors") (part "NPN B1 E2 C3"))
    )
    (comp (ref "T15")
      (value "BC817")
      (footprint "SOT95P230X110-3N")
      (description "NPN Transistor")
      (fields (field (name "MANUFACTURER") "NXP SEMICONDUCTORS") (field (name "AUTHOR") "CERN DEM JLC"))
      (libsource (lib "ICs And Semiconductors") (part "NPN B1 E2 C3"))
    )
    (comp (ref "T16")
      (value "BC817")
      (footprint "SOT95P230X110-3N")
      (description "NPN Transistor")
      (fields (field (name "MANUFACTURER") "NXP SEMICONDUCTORS") (field (name "AUTHOR") "CERN DEM JLC"))
      (libsource (lib "ICs And Semiconductors") (part "NPN B1 E2 C3"))
    )
    (comp (ref "Tp1")
      (value "Test_point")
      (footprint "fromST:TP_C40")
      (description "Test point")
      (fields (field (name "PUBLISHER") "Altium Limited"))
      (libsource (lib "Sajad_Altium_Library") (part "Test point"))
    )
    (comp (ref "Tp2")
      (value "Test_point")
      (footprint "fromST:TP_C40")
      (description "Test point")
      (fields (field (name "PUBLISHER") "Altium Limited"))
      (libsource (lib "Sajad_Altium_Library") (part "Test point"))
    )
    (comp (ref "Tp3")
      (value "Test_point")
      (footprint "fromST:TP_C40")
      (description "Test point")
      (fields (field (name "PUBLISHER") "Altium Limited"))
      (libsource (lib "Sajad_Altium_Library") (part "Test point"))
    )
    (comp (ref "Tp4")
      (value "Test_point")
      (footprint "fromST:TP_C40")
      (description "Test point")
      (fields (field (name "PUBLISHER") "Altium Limited"))
      (libsource (lib "Sajad_Altium_Library") (part "Test point"))
    )
    (comp (ref "Tp5")
      (value "Test_point")
      (footprint "fromST:TP_C40")
      (description "Test point")
      (fields (field (name "PUBLISHER") "Altium Limited"))
      (libsource (lib "Sajad_Altium_Library") (part "Test point"))
    )
    (comp (ref "Tp6")
      (value "Test_point")
      (footprint "fromST:TP_C40")
      (description "Test point")
      (fields (field (name "PUBLISHER") "Altium Limited"))
      (libsource (lib "Sajad_Altium_Library") (part "Test point"))
    )
    (comp (ref "Tp7")
      (value "Test_point")
      (footprint "fromST:TP_C40")
      (description "Test point")
      (fields (field (name "PUBLISHER") "Altium Limited"))
      (libsource (lib "Sajad_Altium_Library") (part "Test point"))
    )
    (comp (ref "Tp8")
      (value "Test_point")
      (footprint "fromST:TP_C40")
      (description "Test point")
      (fields (field (name "PUBLISHER") "Altium Limited"))
      (libsource (lib "Sajad_Altium_Library") (part "Test point"))
    )
    (comp (ref "Tp9")
      (value "Test_point")
      (footprint "fromST:TP_C40")
      (description "Test point")
      (fields (field (name "PUBLISHER") "Altium Limited"))
      (libsource (lib "Sajad_Altium_Library") (part "Test point"))
    )
    (comp (ref "Tp10")
      (value "Test_point")
      (footprint "fromST:TP_C40")
      (description "Test point")
      (fields (field (name "PUBLISHER") "Altium Limited"))
      (libsource (lib "Sajad_Altium_Library") (part "Test point"))
    )
    (comp (ref "Tp11")
      (value "Test_point")
      (footprint "fromST:TP_C40")
      (description "Test point")
      (fields (field (name "PUBLISHER") "Altium Limited"))
      (libsource (lib "Sajad_Altium_Library") (part "Test point"))
    )
    (comp (ref "Tp12")
      (value "Test_point")
      (footprint "fromST:TP_C40")
      (description "Test point")
      (fields (field (name "PUBLISHER") "Altium Limited"))
      (libsource (lib "Sajad_Altium_Library") (part "Test point"))
    )
    (comp (ref "Tp13")
      (value "Test_point")
      (footprint "fromST:TP_C40")
      (description "Test point")
      (fields (field (name "PUBLISHER") "Altium Limited"))
      (libsource (lib "Sajad_Altium_Library") (part "Test point"))
    )
    (comp (ref "Tp14")
      (value "Test_point")
      (footprint "fromST:TP_C40")
      (description "Test point")
      (fields (field (name "PUBLISHER") "Altium Limited"))
      (libsource (lib "Sajad_Altium_Library") (part "Test point"))
    )
    (comp (ref "Tp15")
      (value "Test_point")
      (footprint "fromST:TP_C40")
      (description "Test point")
      (fields (field (name "PUBLISHER") "Altium Limited"))
      (libsource (lib "Sajad_Altium_Library") (part "Test point"))
    )
    (comp (ref "Tp16")
      (value "Test_point")
      (footprint "fromST:TP_C40")
      (description "Test point")
      (fields (field (name "PUBLISHER") "Altium Limited"))
      (libsource (lib "Sajad_Altium_Library") (part "Test point"))
    )
    (comp (ref "Tp17")
      (value "Test_point")
      (footprint "fromST:TP_C40")
      (description "Test point")
      (fields (field (name "PUBLISHER") "Altium Limited"))
      (libsource (lib "Sajad_Altium_Library") (part "Test point"))
    )
    (comp (ref "Tp18")
      (value "Test_point")
      (footprint "fromST:TP_C40")
      (description "Test point")
      (fields (field (name "PUBLISHER") "Altium Limited"))
      (libsource (lib "Sajad_Altium_Library") (part "Test point"))
    )
    (comp (ref "Tp19")
      (value "Test_point")
      (footprint "fromST:TP_C40")
      (description "Test point")
      (fields (field (name "PUBLISHER") "Altium Limited"))
      (libsource (lib "Sajad_Altium_Library") (part "Test point"))
    )
    (comp (ref "Tp20")
      (value "Test_point")
      (footprint "fromST:TP_C40")
      (description "Test point")
      (fields (field (name "PUBLISHER") "Altium Limited"))
      (libsource (lib "Sajad_Altium_Library") (part "Test point"))
    )
    (comp (ref "Tp21")
      (value "Test_point")
      (footprint "fromST:TP_C40")
      (description "Test point")
      (fields (field (name "PUBLISHER") "Altium Limited"))
      (libsource (lib "Sajad_Altium_Library") (part "Test point"))
    )
    (comp (ref "Tp22")
      (value "Test_point")
      (footprint "fromST:TP_C40")
      (description "Test point")
      (fields (field (name "PUBLISHER") "Altium Limited"))
      (libsource (lib "Sajad_Altium_Library") (part "Test point"))
    )
    (comp (ref "Tp23")
      (value "Test_point")
      (footprint "fromST:TP_C40")
      (description "Test point")
      (fields (field (name "PUBLISHER") "Altium Limited"))
      (libsource (lib "Sajad_Altium_Library") (part "Test point"))
    )
    (comp (ref "Tp24")
      (value "Test_point")
      (footprint "fromST:TP_C40")
      (description "Test point")
      (fields (field (name "PUBLISHER") "Altium Limited"))
      (libsource (lib "Sajad_Altium_Library") (part "Test point"))
    )
  )
  (nets
    (net (code "1") (name "+3.3V") (class "Default")
      (node (ref "D1") (pin "2") (pinfunction "C_2") (pintype "passive"))
      (node (ref "D10") (pin "2") (pinfunction "C_2") (pintype "passive"))
      (node (ref "D11") (pin "2") (pinfunction "C_2") (pintype "passive"))
      (node (ref "D12") (pin "2") (pinfunction "C_2") (pintype "passive"))
      (node (ref "D4") (pin "2") (pinfunction "C_2") (pintype "passive"))
      (node (ref "D5") (pin "2") (pinfunction "C_2") (pintype "passive"))
      (node (ref "D6") (pin "2") (pinfunction "C_2") (pintype "passive"))
      (node (ref "D7") (pin "2") (pinfunction "C_2") (pintype "passive"))
    )
    (net (code "2") (name "/SensorCathode1") (class "Default")
      (node (ref "R13") (pin "1") (pinfunction "1_1") (pintype "passive"))
      (node (ref "R5") (pin "2") (pinfunction "2_2") (pintype "passive"))
    )
    (net (code "3") (name "/SensorCathode2") (class "Default")
      (node (ref "R14") (pin "1") (pinfunction "1_1") (pintype "passive"))
      (node (ref "R7") (pin "2") (pinfunction "2_2") (pintype "passive"))
    )
    (net (code "4") (name "/SensorCathode3") (class "Default")
      (node (ref "R15") (pin "1") (pinfunction "1_1") (pintype "passive"))
      (node (ref "R9") (pin "2") (pinfunction "2_2") (pintype "passive"))
    )
    (net (code "5") (name "/SensorCathode4") (class "Default")
      (node (ref "R11") (pin "2") (pinfunction "2_2") (pintype "passive"))
      (node (ref "R16") (pin "1") (pinfunction "1_1") (pintype "passive"))
    )
    (net (code "6") (name "/SensorCathode5") (class "Default")
      (node (ref "R21") (pin "2") (pinfunction "2_2") (pintype "passive"))
      (node (ref "R29") (pin "1") (pinfunction "1_1") (pintype "passive"))
    )
    (net (code "7") (name "/SensorCathode6") (class "Default")
      (node (ref "R23") (pin "2") (pinfunction "2_2") (pintype "passive"))
      (node (ref "R30") (pin "1") (pinfunction "1_1") (pintype "passive"))
    )
    (net (code "8") (name "/SensorCathode7") (class "Default")
      (node (ref "R25") (pin "2") (pinfunction "2_2") (pintype "passive"))
      (node (ref "R31") (pin "1") (pinfunction "1_1") (pintype "passive"))
    )
    (net (code "9") (name "/SensorCathode8") (class "Default")
      (node (ref "R27") (pin "2") (pinfunction "2_2") (pintype "passive"))
      (node (ref "R32") (pin "1") (pinfunction "1_1") (pintype "passive"))
    )
    (net (code "10") (name "/SensorCathode9") (class "Default")
      (node (ref "R37") (pin "2") (pinfunction "2_2") (pintype "passive"))
      (node (ref "R45") (pin "1") (pinfunction "1_1") (pintype "passive"))
    )
    (net (code "11") (name "/SensorCathode10") (class "Default")
      (node (ref "R39") (pin "2") (pinfunction "2_2") (pintype "passive"))
      (node (ref "R46") (pin "1") (pinfunction "1_1") (pintype "passive"))
    )
    (net (code "12") (name "/SensorCathode11") (class "Default")
      (node (ref "R41") (pin "2") (pinfunction "2_2") (pintype "passive"))
      (node (ref "R47") (pin "1") (pinfunction "1_1") (pintype "passive"))
    )
    (net (code "13") (name "/SensorCathode12") (class "Default")
      (node (ref "R43") (pin "2") (pinfunction "2_2") (pintype "passive"))
      (node (ref "R48") (pin "1") (pinfunction "1_1") (pintype "passive"))
    )
    (net (code "14") (name "/SensorCathode13") (class "Default")
      (node (ref "R53") (pin "2") (pinfunction "2_2") (pintype "passive"))
      (node (ref "R61") (pin "1") (pinfunction "1_1") (pintype "passive"))
    )
    (net (code "15") (name "/SensorCathode14") (class "Default")
      (node (ref "R55") (pin "2") (pinfunction "2_2") (pintype "passive"))
      (node (ref "R62") (pin "1") (pinfunction "1_1") (pintype "passive"))
    )
    (net (code "16") (name "/SensorCathode15") (class "Default")
      (node (ref "R57") (pin "2") (pinfunction "2_2") (pintype "passive"))
      (node (ref "R63") (pin "1") (pinfunction "1_1") (pintype "passive"))
    )
    (net (code "17") (name "/SensorCathode16") (class "Default")
      (node (ref "R59") (pin "2") (pinfunction "2_2") (pintype "passive"))
      (node (ref "R64") (pin "1") (pinfunction "1_1") (pintype "passive"))
    )
    (net (code "19") (name "/SensorEnable1") (class "Default")
      (node (ref "R1") (pin "1") (pinfunction "1_1") (pintype "passive"))
    )
    (net (code "20") (name "/SensorEnable2") (class "Default")
      (node (ref "R2") (pin "1") (pinfunction "1_1") (pintype "passive"))
    )
    (net (code "21") (name "/SensorEnable3") (class "Default")
      (node (ref "R3") (pin "1") (pinfunction "1_1") (pintype "passive"))
    )
    (net (code "22") (name "/SensorEnable4") (class "Default")
      (node (ref "R4") (pin "1") (pinfunction "1_1") (pintype "passive"))
    )
    (net (code "23") (name "/SensorEnable5") (class "Default")
      (node (ref "R17") (pin "1") (pinfunction "1_1") (pintype "passive"))
    )
    (net (code "24") (name "/SensorEnable6") (class "Default")
      (node (ref "R18") (pin "1") (pinfunction "1_1") (pintype "passive"))
    )
    (net (code "25") (name "/SensorEnable7") (class "Default")
      (node (ref "R19") (pin "1") (pinfunction "1_1") (pintype "passive"))
    )
    (net (code "26") (name "/SensorEnable8") (class "Default")
      (node (ref "R20") (pin "1") (pinfunction "1_1") (pintype "passive"))
    )
    (net (code "27") (name "/SensorEnable9") (class "Default")
      (node (ref "R33") (pin "1") (pinfunction "1_1") (pintype "passive"))
    )
    (net (code "28") (name "/SensorEnable10") (class "Default")
      (node (ref "R34") (pin "1") (pinfunction "1_1") (pintype "passive"))
    )
    (net (code "29") (name "/SensorEnable11") (class "Default")
      (node (ref "R35") (pin "1") (pinfunction "1_1") (pintype "passive"))
    )
    (net (code "30") (name "/SensorEnable12") (class "Default")
      (node (ref "R36") (pin "1") (pinfunction "1_1") (pintype "passive"))
    )
    (net (code "31") (name "/SensorEnable13") (class "Default")
      (node (ref "R49") (pin "1") (pinfunction "1_1") (pintype "passive"))
    )
    (net (code "32") (name "/SensorEnable14") (class "Default")
      (node (ref "R50") (pin "1") (pinfunction "1_1") (pintype "passive"))
    )
    (net (code "33") (name "/SensorEnable15") (class "Default")
      (node (ref "R51") (pin "1") (pinfunction "1_1") (pintype "passive"))
    )
    (net (code "34") (name "/SensorEnable16") (class "Default")
      (node (ref "R52") (pin "1") (pinfunction "1_1") (pintype "passive"))
    )
    (net (code "36") (name "/SensorSignal1") (class "Default")
      (node (ref "C1") (pin "2") (pinfunction "2_2") (pintype "passive"))
      (node (ref "D1") (pin "3") (pinfunction "COMAC_3") (pintype "passive"))
      (node (ref "D2") (pin "3") (pinfunction "COMC_3") (pintype "passive"))
      (node (ref "Tp5") (pin "1") (pinfunction "1_1") (pintype "passive"))
    )
    (net (code "37") (name "/SensorSignal2") (class "Default")
      (node (ref "C2") (pin "2") (pinfunction "2_2") (pintype "passive"))
      (node (ref "D3") (pin "3") (pinfunction "COMC_3") (pintype "passive"))
      (node (ref "D4") (pin "3") (pinfunction "COMAC_3") (pintype "passive"))
      (node (ref "Tp6") (pin "1") (pinfunction "1_1") (pintype "passive"))
    )
    (net (code "38") (name "/SensorSignal3") (class "Default")
      (node (ref "C3") (pin "2") (pinfunction "2_2") (pintype "passive"))
      (node (ref "D5") (pin "3") (pinfunction "COMAC_3") (pintype "passive"))
      (node (ref "D8") (pin "3") (pinfunction "COMC_3") (pintype "passive"))
      (node (ref "Tp7") (pin "1") (pinfunction "1_1") (pintype "passive"))
    )
    (net (code "39") (name "/SensorSignal4") (class "Default")
      (node (ref "C4") (pin "2") (pinfunction "2_2") (pintype "passive"))
      (node (ref "D6") (pin "3") (pinfunction "COMAC_3") (pintype "passive"))
      (node (ref "D9") (pin "3") (pinfunction "COMC_3") (pintype "passive"))
      (node (ref "Tp8") (pin "1") (pinfunction "1_1") (pintype "passive"))
    )
    (net (code "40") (name "/SensorSignal5") (class "Default")
      (node (ref "C5") (pin "2") (pinfunction "2_2") (pintype "passive"))
      (node (ref "D13") (pin "3") (pinfunction "COMC_3") (pintype "passive"))
      (node (ref "D7") (pin "3") (pinfunction "COMAC_3") (pintype "passive"))
      (node (ref "Tp13") (pin "1") (pinfunction "1_1") (pintype "passive"))
    )
    (net (code "41") (name "/SensorSignal6") (class "Default")
      (node (ref "C6") (pin "2") (pinfunction "2_2") (pintype "passive"))
      (node (ref "D10") (pin "3") (pinfunction "COMAC_3") (pintype "passive"))
      (node (ref "D14") (pin "3") (pinfunction "COMC_3") (pintype "passive"))
      (node (ref "Tp14") (pin "1") (pinfunction "1_1") (pintype "passive"))
    )
    (net (code "42") (name "/SensorSignal7") (class "Default")
      (node (ref "C7") (pin "2") (pinfunction "2_2") (pintype "passive"))
      (node (ref "D11") (pin "3") (pinfunction "COMAC_3") (pintype "passive"))
      (node (ref "D15") (pin "3") (pinfunction "COMC_3") (pintype "passive"))
      (node (ref "Tp15") (pin "1") (pinfunction "1_1") (pintype "passive"))
    )
    (net (code "43") (name "/SensorSignal8") (class "Default")
      (node (ref "C8") (pin "2") (pinfunction "2_2") (pintype "passive"))
      (node (ref "D12") (pin "3") (pinfunction "COMAC_3") (pintype "passive"))
      (node (ref "D16") (pin "3") (pinfunction "COMC_3") (pintype "passive"))
      (node (ref "Tp20") (pin "1") (pinfunction "1_1") (pintype "passive"))
    )
    (net (code "45") (name "GND") (class "Default")
      (node (ref "C1") (pin "1") (pinfunction "1_1") (pintype "passive"))
      (node (ref "C2") (pin "1") (pinfunction "1_1") (pintype "passive"))
      (node (ref "C3") (pin "1") (pinfunction "1_1") (pintype "passive"))
      (node (ref "C4") (pin "1") (pinfunction "1_1") (pintype "passive"))
      (node (ref "C5") (pin "1") (pinfunction "1_1") (pintype "passive"))
      (node (ref "C6") (pin "1") (pinfunction "1_1") (pintype "passive"))
      (node (ref "C7") (pin "1") (pinfunction "1_1") (pintype "passive"))
      (node (ref "C8") (pin "1") (pinfunction "1_1") (pintype "passive"))
      (node (ref "D1") (pin "1") (pinfunction "A_1") (pintype "passive"))
      (node (ref "D10") (pin "1") (pinfunction "A_1") (pintype "passive"))
      (node (ref "D11") (pin "1") (pinfunction "A_1") (pintype "passive"))
      (node (ref "D12") (pin "1") (pinfunction "A_1") (pintype "passive"))
      (node (ref "D4") (pin "1") (pinfunction "A_1") (pintype "passive"))
      (node (ref "D5") (pin "1") (pinfunction "A_1") (pintype "passive"))
      (node (ref "D6") (pin "1") (pinfunction "A_1") (pintype "passive"))
      (node (ref "D7") (pin "1") (pinfunction "A_1") (pintype "passive"))
      (node (ref "R10") (pin "1") (pinfunction "1_1") (pintype "passive"))
      (node (ref "R11") (pin "1") (pinfunction "1_1") (pintype "passive"))
      (node (ref "R12") (pin "1") (pinfunction "1_1") (pintype "passive"))
      (node (ref "R21") (pin "1") (pinfunction "1_1") (pintype "passive"))
      (node (ref "R22") (pin "1") (pinfunction "1_1") (pintype "passive"))
      (node (ref "R23") (pin "1") (pinfunction "1_1") (pintype "passive"))
      (node (ref "R24") (pin "1") (pinfunction "1_1") (pintype "passive"))
      (node (ref "R25") (pin "1") (pinfunction "1_1") (pintype "passive"))
      (node (ref "R26") (pin "1") (pinfunction "1_1") (pintype "passive"))
      (node (ref "R27") (pin "1") (pinfunction "1_1") (pintype "passive"))
      (node (ref "R28") (pin "1") (pinfunction "1_1") (pintype "passive"))
      (node (ref "R37") (pin "1") (pinfunction "1_1") (pintype "passive"))
      (node (ref "R38") (pin "1") (pinfunction "1_1") (pintype "passive"))
      (node (ref "R39") (pin "1") (pinfunction "1_1") (pintype "passive"))
      (node (ref "R40") (pin "1") (pinfunction "1_1") (pintype "passive"))
      (node (ref "R41") (pin "1") (pinfunction "1_1") (pintype "passive"))
      (node (ref "R42") (pin "1") (pinfunction "1_1") (pintype "passive"))
      (node (ref "R43") (pin "1") (pinfunction "1_1") (pintype "passive"))
      (node (ref "R44") (pin "1") (pinfunction "1_1") (pintype "passive"))
      (node (ref "R5") (pin "1") (pinfunction "1_1") (pintype "passive"))
      (node (ref "R53") (pin "1") (pinfunction "1_1") (pintype "passive"))
      (node (ref "R54") (pin "1") (pinfunction "1_1") (pintype "passive"))
      (node (ref "R55") (pin "1") (pinfunction "1_1") (pintype "passive"))
      (node (ref "R56") (pin "1") (pinfunction "1_1") (pintype "passive"))
      (node (ref "R57") (pin "1") (pinfunction "1_1") (pintype "passive"))
      (node (ref "R58") (pin "1") (pinfunction "1_1") (pintype "passive"))
      (node (ref "R59") (pin "1") (pinfunction "1_1") (pintype "passive"))
      (node (ref "R6") (pin "1") (pinfunction "1_1") (pintype "passive"))
      (node (ref "R60") (pin "1") (pinfunction "1_1") (pintype "passive"))
      (node (ref "R7") (pin "1") (pinfunction "1_1") (pintype "passive"))
      (node (ref "R8") (pin "1") (pinfunction "1_1") (pintype "passive"))
      (node (ref "R9") (pin "1") (pinfunction "1_1") (pintype "passive"))
      (node (ref "T1") (pin "2") (pinfunction "E_2") (pintype "passive"))
      (node (ref "T10") (pin "2") (pinfunction "E_2") (pintype "passive"))
      (node (ref "T11") (pin "2") (pinfunction "E_2") (pintype "passive"))
      (node (ref "T12") (pin "2") (pinfunction "E_2") (pintype "passive"))
      (node (ref "T13") (pin "2") (pinfunction "E_2") (pintype "passive"))
      (node (ref "T14") (pin "2") (pinfunction "E_2") (pintype "passive"))
      (node (ref "T15") (pin "2") (pinfunction "E_2") (pintype "passive"))
      (node (ref "T16") (pin "2") (pinfunction "E_2") (pintype "passive"))
      (node (ref "T2") (pin "2") (pinfunction "E_2") (pintype "passive"))
      (node (ref "T3") (pin "2") (pinfunction "E_2") (pintype "passive"))
      (node (ref "T4") (pin "2") (pinfunction "E_2") (pintype "passive"))
      (node (ref "T5") (pin "2") (pinfunction "E_2") (pintype "passive"))
      (node (ref "T6") (pin "2") (pinfunction "E_2") (pintype "passive"))
      (node (ref "T7") (pin "2") (pinfunction "E_2") (pintype "passive"))
      (node (ref "T8") (pin "2") (pinfunction "E_2") (pintype "passive"))
      (node (ref "T9") (pin "2") (pinfunction "E_2") (pintype "passive"))
    )
    (net (code "46") (name "Net-(D2A-A)") (class "Default")
      (node (ref "D2") (pin "1") (pinfunction "A_1") (pintype "passive"))
      (node (ref "R13") (pin "2") (pinfunction "2_2") (pintype "passive"))
      (node (ref "T1") (pin "3") (pinfunction "C_3") (pintype "passive"))
      (node (ref "Tp1") (pin "1") (pinfunction "1_1") (pintype "passive"))
    )
    (net (code "47") (name "Net-(D2B-A)") (class "Default")
      (node (ref "D2") (pin "2") (pinfunction "A_2") (pintype "passive"))
      (node (ref "R14") (pin "2") (pinfunction "2_2") (pintype "passive"))
      (node (ref "T2") (pin "3") (pinfunction "C_3") (pintype "passive"))
      (node (ref "Tp2") (pin "1") (pinfunction "1_1") (pintype "passive"))
    )
    (net (code "48") (name "Net-(D3A-A)") (class "Default")
      (node (ref "D3") (pin "1") (pinfunction "A_1") (pintype "passive"))
      (node (ref "R15") (pin "2") (pinfunction "2_2") (pintype "passive"))
      (node (ref "T3") (pin "3") (pinfunction "C_3") (pintype "passive"))
      (node (ref "Tp3") (pin "1") (pinfunction "1_1") (pintype "passive"))
    )
    (net (code "49") (name "Net-(D3B-A)") (class "Default")
      (node (ref "D3") (pin "2") (pinfunction "A_2") (pintype "passive"))
      (node (ref "R16") (pin "2") (pinfunction "2_2") (pintype "passive"))
      (node (ref "T4") (pin "3") (pinfunction "C_3") (pintype "passive"))
      (node (ref "Tp4") (pin "1") (pinfunction "1_1") (pintype "passive"))
    )
    (net (code "50") (name "Net-(D8A-A)") (class "Default")
      (node (ref "D8") (pin "1") (pinfunction "A_1") (pintype "passive"))
      (node (ref "R29") (pin "2") (pinfunction "2_2") (pintype "passive"))
      (node (ref "T5") (pin "3") (pinfunction "C_3") (pintype "passive"))
      (node (ref "Tp9") (pin "1") (pinfunction "1_1") (pintype "passive"))
    )
    (net (code "51") (name "Net-(D8B-A)") (class "Default")
      (node (ref "D8") (pin "2") (pinfunction "A_2") (pintype "passive"))
      (node (ref "R30") (pin "2") (pinfunction "2_2") (pintype "passive"))
      (node (ref "T6") (pin "3") (pinfunction "C_3") (pintype "passive"))
      (node (ref "Tp10") (pin "1") (pinfunction "1_1") (pintype "passive"))
    )
    (net (code "52") (name "Net-(D9A-A)") (class "Default")
      (node (ref "D9") (pin "1") (pinfunction "A_1") (pintype "passive"))
      (node (ref "R31") (pin "2") (pinfunction "2_2") (pintype "passive"))
      (node (ref "T7") (pin "3") (pinfunction "C_3") (pintype "passive"))
      (node (ref "Tp11") (pin "1") (pinfunction "1_1") (pintype "passive"))
    )
    (net (code "53") (name "Net-(D9B-A)") (class "Default")
      (node (ref "D9") (pin "2") (pinfunction "A_2") (pintype "passive"))
      (node (ref "R32") (pin "2") (pinfunction "2_2") (pintype "passive"))
      (node (ref "T8") (pin "3") (pinfunction "C_3") (pintype "passive"))
      (node (ref "Tp12") (pin "1") (pinfunction "1_1") (pintype "passive"))
    )
    (net (code "54") (name "Net-(D13A-A)") (class "Default")
      (node (ref "D13") (pin "1") (pinfunction "A_1") (pintype "passive"))
      (node (ref "R45") (pin "2") (pinfunction "2_2") (pintype "passive"))
      (node (ref "T9") (pin "3") (pinfunction "C_3") (pintype "passive"))
      (node (ref "Tp16") (pin "1") (pinfunction "1_1") (pintype "passive"))
    )
    (net (code "55") (name "Net-(D13B-A)") (class "Default")
      (node (ref "D13") (pin "2") (pinfunction "A_2") (pintype "passive"))
      (node (ref "R46") (pin "2") (pinfunction "2_2") (pintype "passive"))
      (node (ref "T10") (pin "3") (pinfunction "C_3") (pintype "passive"))
      (node (ref "Tp17") (pin "1") (pinfunction "1_1") (pintype "passive"))
    )
    (net (code "56") (name "Net-(D14A-A)") (class "Default")
      (node (ref "D14") (pin "1") (pinfunction "A_1") (pintype "passive"))
      (node (ref "R47") (pin "2") (pinfunction "2_2") (pintype "passive"))
      (node (ref "T11") (pin "3") (pinfunction "C_3") (pintype "passive"))
      (node (ref "Tp18") (pin "1") (pinfunction "1_1") (pintype "passive"))
    )
    (net (code "57") (name "Net-(D14B-A)") (class "Default")
      (node (ref "D14") (pin "2") (pinfunction "A_2") (pintype "passive"))
      (node (ref "R48") (pin "2") (pinfunction "2_2") (pintype "passive"))
      (node (ref "T12") (pin "3") (pinfunction "C_3") (pintype "passive"))
      (node (ref "Tp19") (pin "1") (pinfunction "1_1") (pintype "passive"))
    )
    (net (code "58") (name "Net-(D15A-A)") (class "Default")
      (node (ref "D15") (pin "1") (pinfunction "A_1") (pintype "passive"))
      (node (ref "R61") (pin "2") (pinfunction "2_2") (pintype "passive"))
      (node (ref "T13") (pin "3") (pinfunction "C_3") (pintype "passive"))
      (node (ref "Tp21") (pin "1") (pinfunction "1_1") (pintype "passive"))
    )
    (net (code "59") (name "Net-(D15B-A)") (class "Default")
      (node (ref "D15") (pin "2") (pinfunction "A_2") (pintype "passive"))
      (node (ref "R62") (pin "2") (pinfunction "2_2") (pintype "passive"))
      (node (ref "T14") (pin "3") (pinfunction "C_3") (pintype "passive"))
      (node (ref "Tp22") (pin "1") (pinfunction "1_1") (pintype "passive"))
    )
    (net (code "60") (name "Net-(D16A-A)") (class "Default")
      (node (ref "D16") (pin "1") (pinfunction "A_1") (pintype "passive"))
      (node (ref "R63") (pin "2") (pinfunction "2_2") (pintype "passive"))
      (node (ref "T15") (pin "3") (pinfunction "C_3") (pintype "passive"))
      (node (ref "Tp23") (pin "1") (pinfunction "1_1") (pintype "passive"))
    )
    (net (code "61") (name "Net-(D16B-A)") (class "Default")
      (node (ref "D16") (pin "2") (pinfunction "A_2") (pintype "passive"))
      (node (ref "R64") (pin "2") (pinfunction "2_2") (pintype "passive"))
      (node (ref "T16") (pin "3") (pinfunction "C_3") (pintype "passive"))
      (node (ref "Tp24") (pin "1") (pinfunction "1_1") (pintype "passive"))
    )
    (net (code "62") (name "Net-(T1-B)") (class "Default")
      (node (ref "R1") (pin "2") (pinfunction "2_2") (pintype "passive"))
      (node (ref "R6") (pin "2") (pinfunction "2_2") (pintype "passive"))
      (node (ref "T1") (pin "1") (pinfunction "B_1") (pintype "passive"))
    )
    (net (code "63") (name "Net-(T2-B)") (class "Default")
      (node (ref "R2") (pin "2") (pinfunction "2_2") (pintype "passive"))
      (node (ref "R8") (pin "2") (pinfunction "2_2") (pintype "passive"))
      (node (ref "T2") (pin "1") (pinfunction "B_1") (pintype "passive"))
    )
    (net (code "64") (name "Net-(T3-B)") (class "Default")
      (node (ref "R10") (pin "2") (pinfunction "2_2") (pintype "passive"))
      (node (ref "R3") (pin "2") (pinfunction "2_2") (pintype "passive"))
      (node (ref "T3") (pin "1") (pinfunction "B_1") (pintype "passive"))
    )
    (net (code "65") (name "Net-(T4-B)") (class "Default")
      (node (ref "R12") (pin "2") (pinfunction "2_2") (pintype "passive"))
      (node (ref "R4") (pin "2") (pinfunction "2_2") (pintype "passive"))
      (node (ref "T4") (pin "1") (pinfunction "B_1") (pintype "passive"))
    )
    (net (code "66") (name "Net-(T5-B)") (class "Default")
      (node (ref "R17") (pin "2") (pinfunction "2_2") (pintype "passive"))
      (node (ref "R22") (pin "2") (pinfunction "2_2") (pintype "passive"))
      (node (ref "T5") (pin "1") (pinfunction "B_1") (pintype "passive"))
    )
    (net (code "67") (name "Net-(T6-B)") (class "Default")
      (node (ref "R18") (pin "2") (pinfunction "2_2") (pintype "passive"))
      (node (ref "R24") (pin "2") (pinfunction "2_2") (pintype "passive"))
      (node (ref "T6") (pin "1") (pinfunction "B_1") (pintype "passive"))
    )
    (net (code "68") (name "Net-(T7-B)") (class "Default")
      (node (ref "R19") (pin "2") (pinfunction "2_2") (pintype "passive"))
      (node (ref "R26") (pin "2") (pinfunction "2_2") (pintype "passive"))
      (node (ref "T7") (pin "1") (pinfunction "B_1") (pintype "passive"))
    )
    (net (code "69") (name "Net-(T8-B)") (class "Default")
      (node (ref "R20") (pin "2") (pinfunction "2_2") (pintype "passive"))
      (node (ref "R28") (pin "2") (pinfunction "2_2") (pintype "passive"))
      (node (ref "T8") (pin "1") (pinfunction "B_1") (pintype "passive"))
    )
    (net (code "70") (name "Net-(T9-B)") (class "Default")
      (node (ref "R33") (pin "2") (pinfunction "2_2") (pintype "passive"))
      (node (ref "R38") (pin "2") (pinfunction "2_2") (pintype "passive"))
      (node (ref "T9") (pin "1") (pinfunction "B_1") (pintype "passive"))
    )
    (net (code "71") (name "Net-(T10-B)") (class "Default")
      (node (ref "R34") (pin "2") (pinfunction "2_2") (pintype "passive"))
      (node (ref "R40") (pin "2") (pinfunction "2_2") (pintype "passive"))
      (node (ref "T10") (pin "1") (pinfunction "B_1") (pintype "passive"))
    )
    (net (code "72") (name "Net-(T11-B)") (class "Default")
      (node (ref "R35") (pin "2") (pinfunction "2_2") (pintype "passive"))
      (node (ref "R42") (pin "2") (pinfunction "2_2") (pintype "passive"))
      (node (ref "T11") (pin "1") (pinfunction "B_1") (pintype "passive"))
    )
    (net (code "73") (name "Net-(T12-B)") (class "Default")
      (node (ref "R36") (pin "2") (pinfunction "2_2") (pintype "passive"))
      (node (ref "R44") (pin "2") (pinfunction "2_2") (pintype "passive"))
      (node (ref "T12") (pin "1") (pinfunction "B_1") (pintype "passive"))
    )
    (net (code "74") (name "Net-(T13-B)") (class "Default")
      (node (ref "R49") (pin "2") (pinfunction "2_2") (pintype "passive"))
      (node (ref "R54") (pin "2") (pinfunction "2_2") (pintype "passive"))
      (node (ref "T13") (pin "1") (pinfunction "B_1") (pintype "passive"))
    )
    (net (code "75") (name "Net-(T14-B)") (class "Default")
      (node (ref "R50") (pin "2") (pinfunction "2_2") (pintype "passive"))
      (node (ref "R56") (pin "2") (pinfunction "2_2") (pintype "passive"))
      (node (ref "T14") (pin "1") (pinfunction "B_1") (pintype "passive"))
    )
    (net (code "76") (name "Net-(T15-B)") (class "Default")
      (node (ref "R51") (pin "2") (pinfunction "2_2") (pintype "passive"))
      (node (ref "R58") (pin "2") (pinfunction "2_2") (pintype "passive"))
      (node (ref "T15") (pin "1") (pinfunction "B_1") (pintype "passive"))
    )
    (net (code "77") (name "Net-(T16-B)") (class "Default")
      (node (ref "R52") (pin "2") (pinfunction "2_2") (pintype "passive"))
      (node (ref "R60") (pin "2") (pinfunction "2_2") (pintype "passive"))
      (node (ref "T16") (pin "1") (pinfunction "B_1") (pintype "passive"))
    )
  )
)
